# v100_ripping.net
KiCad netlist of a schematic drawn in EAGLE
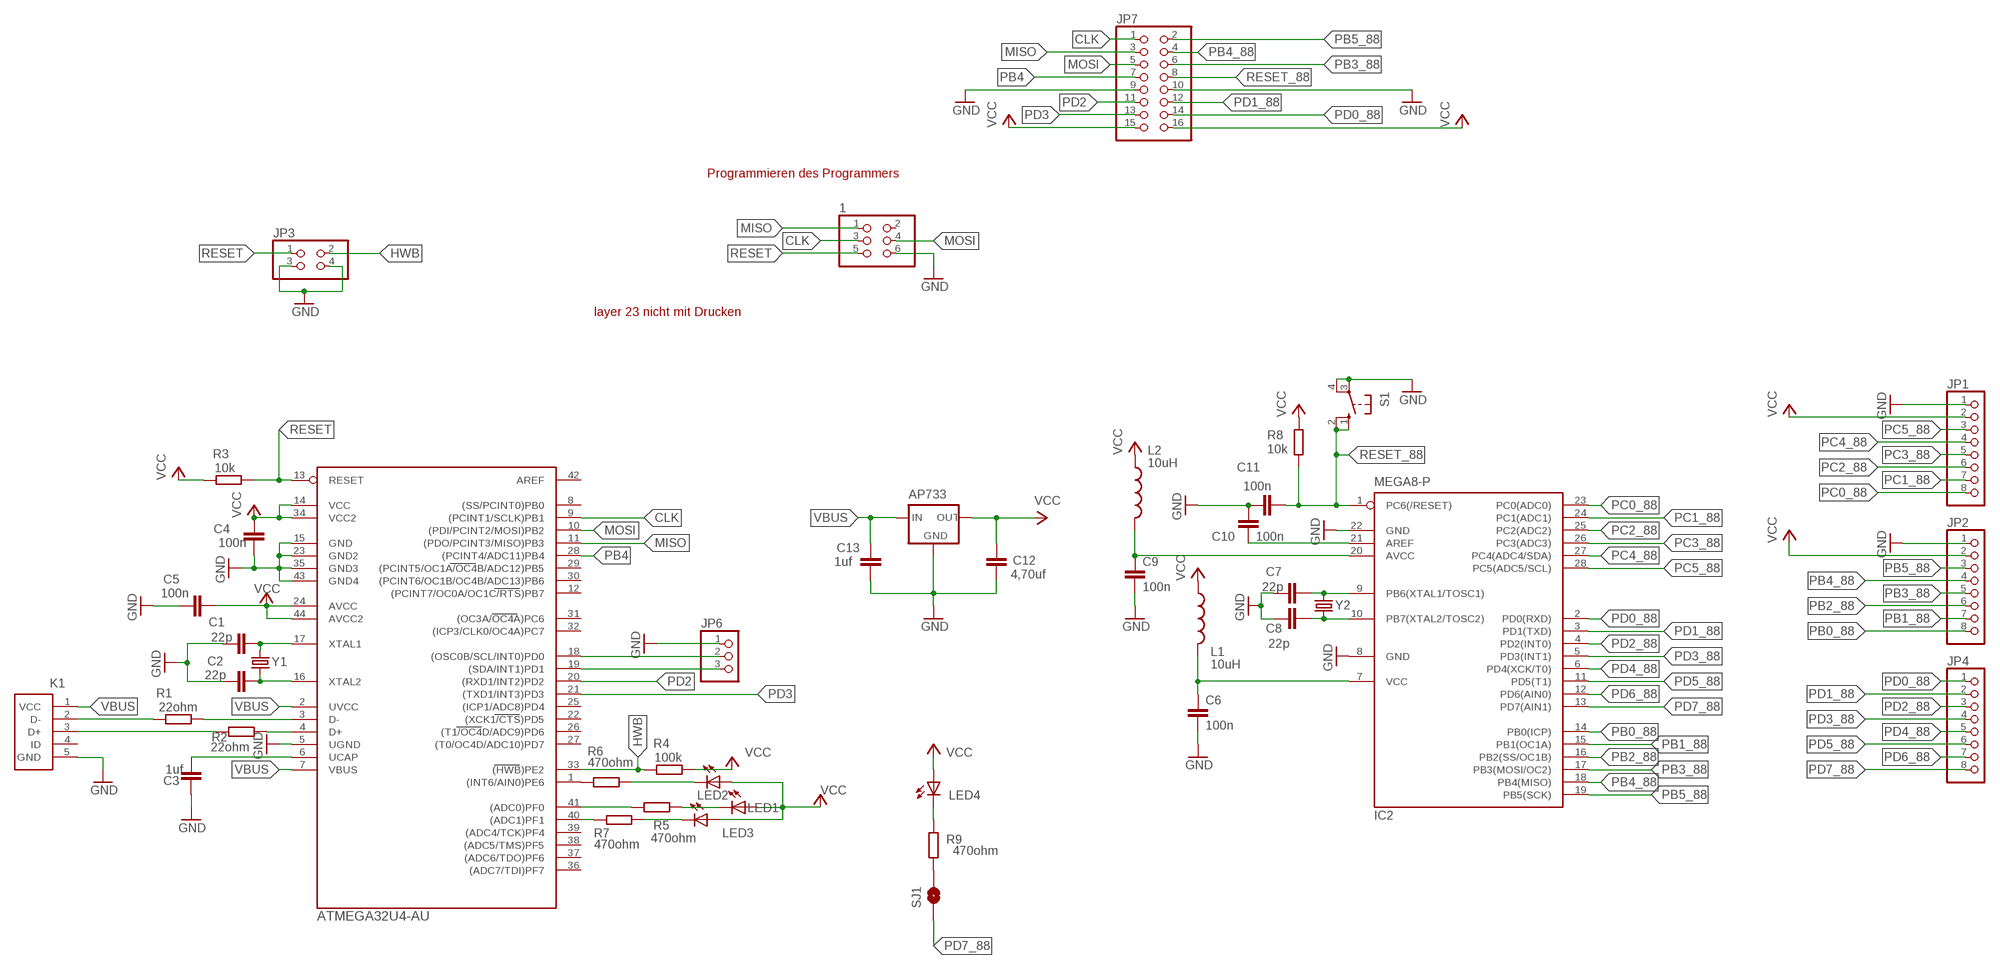
[diagram p0: schematic, sheet 1]

(export (version "E")
  (design (tool "Eeschema 10.0.6"))
  (components
    (comp (ref "1")
      (value "PINHD-2X3")
      (footprint "eagle-import:2X03")
      (libsource (lib "eagle-import") (part "PINHD-2X3"))
    )
    (comp (ref "C1")
      (value "22p")
      (footprint "eagle-import:C0805")
      (libsource (lib "eagle-import") (part "C-EUC0805"))
    )
    (comp (ref "C2")
      (value "22p")
      (footprint "eagle-import:C0805")
      (libsource (lib "eagle-import") (part "C-EUC0805"))
    )
    (comp (ref "C3")
      (value "1uf")
      (footprint "eagle-import:C0805")
      (libsource (lib "eagle-import") (part "C-EUC0805"))
    )
    (comp (ref "C4")
      (value "100n")
      (footprint "eagle-import:C0805")
      (libsource (lib "eagle-import") (part "C-EUC0805"))
    )
    (comp (ref "C5")
      (value "100n")
      (footprint "eagle-import:C0805")
      (libsource (lib "eagle-import") (part "C-EUC0805"))
    )
    (comp (ref "C6")
      (value "100n")
      (footprint "eagle-import:0805")
      (libsource (lib "eagle-import") (part "CAP0805"))
    )
    (comp (ref "C7")
      (value "22p")
      (footprint "eagle-import:C0805")
      (libsource (lib "eagle-import") (part "C-EUC0805"))
    )
    (comp (ref "C8")
      (value "22p")
      (footprint "eagle-import:C0805")
      (libsource (lib "eagle-import") (part "C-EUC0805"))
    )
    (comp (ref "C9")
      (value "100n")
      (footprint "eagle-import:0805")
      (libsource (lib "eagle-import") (part "CAP0805"))
    )
    (comp (ref "C10")
      (value "100n")
      (footprint "eagle-import:0805")
      (libsource (lib "eagle-import") (part "CAP0805"))
    )
    (comp (ref "C11")
      (value "100n")
      (footprint "eagle-import:0805")
      (libsource (lib "eagle-import") (part "CAP0805"))
    )
    (comp (ref "C12")
      (value "4,70uf")
      (footprint "eagle-import:C0805")
      (libsource (lib "eagle-import") (part "C-EUC0805"))
    )
    (comp (ref "C13")
      (value "1uf")
      (footprint "eagle-import:C0805")
      (libsource (lib "eagle-import") (part "C-EUC0805"))
    )
    (comp (ref "IC1")
      (value "ATMEGA32U4-AU")
      (footprint "eagle-import:TQFP44")
      (libsource (lib "eagle-import") (part "ATMEGA32U4-AU"))
    )
    (comp (ref "IC2")
      (value "MEGA8-P")
      (footprint "eagle-import:DIL28-3")
      (libsource (lib "eagle-import") (part "MEGA8-P"))
    )
    (comp (ref "JP1")
      (value "PINHD-1X8")
      (footprint "eagle-import:1X08")
      (libsource (lib "eagle-import") (part "PINHD-1X8"))
    )
    (comp (ref "JP2")
      (value "PINHD-1X8")
      (footprint "eagle-import:1X08")
      (libsource (lib "eagle-import") (part "PINHD-1X8"))
    )
    (comp (ref "JP3")
      (value "PINHD-2X2")
      (footprint "eagle-import:2X02")
      (libsource (lib "eagle-import") (part "PINHD-2X2"))
    )
    (comp (ref "JP4")
      (value "PINHD-1X8")
      (footprint "eagle-import:1X08")
      (libsource (lib "eagle-import") (part "PINHD-1X8"))
    )
    (comp (ref "JP6")
      (value "PINHD-1X3")
      (footprint "eagle-import:1X03")
      (libsource (lib "eagle-import") (part "PINHD-1X3"))
    )
    (comp (ref "JP7")
      (value "PINHD-2X8")
      (footprint "eagle-import:2X08")
      (libsource (lib "eagle-import") (part "PINHD-2X8"))
    )
    (comp (ref "K1")
      (value "65100516121")
      (footprint "eagle-import:65100516121")
      (libsource (lib "eagle-import") (part "65100516121"))
    )
    (comp (ref "L1")
      (value "10uH")
      (footprint "eagle-import:0805")
      (libsource (lib "eagle-import") (part "INDUCTOR0805"))
    )
    (comp (ref "L2")
      (value "10uH")
      (footprint "eagle-import:0805")
      (libsource (lib "eagle-import") (part "INDUCTOR0805"))
    )
    (comp (ref "LED1")
      (value "LED_LEDCHIP-LED0805")
      (footprint "eagle-import:LED_CHIP-LED0805")
      (libsource (lib "eagle-import") (part "LED_LEDCHIP-LED0805"))
    )
    (comp (ref "LED2")
      (value "LED_LEDCHIP-LED0805")
      (footprint "eagle-import:LED_CHIP-LED0805")
      (libsource (lib "eagle-import") (part "LED_LEDCHIP-LED0805"))
    )
    (comp (ref "LED3")
      (value "LED_LEDCHIP-LED0805")
      (footprint "eagle-import:LED_CHIP-LED0805")
      (libsource (lib "eagle-import") (part "LED_LEDCHIP-LED0805"))
    )
    (comp (ref "LED4")
      (value "LED_LEDCHIP-LED0805")
      (footprint "eagle-import:LED_CHIP-LED0805")
      (libsource (lib "eagle-import") (part "LED_LEDCHIP-LED0805"))
    )
    (comp (ref "R1")
      (value "22ohm")
      (footprint "eagle-import:R0805")
      (libsource (lib "eagle-import") (part "R-EU_R0805"))
    )
    (comp (ref "R2")
      (value "22ohm")
      (footprint "eagle-import:R0805")
      (libsource (lib "eagle-import") (part "R-EU_R0805"))
    )
    (comp (ref "R3")
      (value "10k")
      (footprint "eagle-import:R0805")
      (libsource (lib "eagle-import") (part "R-EU_R0805"))
    )
    (comp (ref "R4")
      (value "100k")
      (footprint "eagle-import:R0805")
      (libsource (lib "eagle-import") (part "R-EU_R0805"))
    )
    (comp (ref "R5")
      (value "470ohm")
      (footprint "eagle-import:R0805")
      (libsource (lib "eagle-import") (part "R-EU_R0805"))
    )
    (comp (ref "R6")
      (value "470ohm")
      (footprint "eagle-import:R0805")
      (libsource (lib "eagle-import") (part "R-EU_R0805"))
    )
    (comp (ref "R7")
      (value "470ohm")
      (footprint "eagle-import:R0805")
      (libsource (lib "eagle-import") (part "R-EU_R0805"))
    )
    (comp (ref "R8")
      (value "10k")
      (footprint "eagle-import:R0805")
      (libsource (lib "eagle-import") (part "R-EU_R0805"))
    )
    (comp (ref "R9")
      (value "470ohm")
      (footprint "eagle-import:R0805")
      (libsource (lib "eagle-import") (part "R-EU_R0805"))
    )
    (comp (ref "S1")
      (value "SWITCH-OMRON_10-XX")
      (footprint "eagle-import:SWITCH-OMRON_B3F-10XX")
      (fields (field (name "MPN") "B3F-1000"))
      (libsource (lib "eagle-import") (part "SWITCH-OMRON_10-XX"))
    )
    (comp (ref "SJ1")
      (value "SOLDERJUMPERTRACE")
      (footprint "eagle-import:SJ_2S-TRACE")
      (libsource (lib "eagle-import") (part "SOLDERJUMPERTRACE"))
    )
    (comp (ref "U$2")
      (value "AP733")
      (footprint "eagle-import:AP733")
      (libsource (lib "eagle-import") (part "AP733"))
    )
    (comp (ref "Y1")
      (value "CRYSTALSMD")
      (footprint "eagle-import:HC49UP")
      (libsource (lib "eagle-import") (part "CRYSTALSMD"))
    )
    (comp (ref "Y2")
      (value "CRYSTALSMD")
      (footprint "eagle-import:HC49UP")
      (libsource (lib "eagle-import") (part "CRYSTALSMD"))
    )
  )
  (nets
    (net (code "1") (name "CLK") (class "Default")
      (node (ref "1") (pin "3") (pinfunction "3_3") (pintype "passive"))
      (node (ref "IC1") (pin "9") (pinfunction "(PCINT1/SCLK)PB1_9") (pintype "bidirectional"))
      (node (ref "JP7") (pin "1") (pinfunction "1_1") (pintype "passive"))
    )
    (net (code "2") (name "GND") (class "Default")
      (node (ref "1") (pin "6") (pinfunction "6_6") (pintype "passive"))
      (node (ref "C1") (pin "1") (pinfunction "1_1") (pintype "passive"))
      (node (ref "C10") (pin "1") (pinfunction "1_1") (pintype "passive"))
      (node (ref "C11") (pin "1") (pinfunction "1_1") (pintype "passive"))
      (node (ref "C12") (pin "2") (pinfunction "2_2") (pintype "passive"))
      (node (ref "C13") (pin "2") (pinfunction "2_2") (pintype "passive"))
      (node (ref "C2") (pin "1") (pinfunction "1_1") (pintype "passive"))
      (node (ref "C3") (pin "1") (pinfunction "1_1") (pintype "passive"))
      (node (ref "C4") (pin "1") (pinfunction "1_1") (pintype "passive"))
      (node (ref "C5") (pin "2") (pinfunction "2_2") (pintype "passive"))
      (node (ref "C6") (pin "2") (pinfunction "2_2") (pintype "passive"))
      (node (ref "C7") (pin "1") (pinfunction "1_1") (pintype "passive"))
      (node (ref "C8") (pin "1") (pinfunction "1_1") (pintype "passive"))
      (node (ref "C9") (pin "2") (pinfunction "2_2") (pintype "passive"))
      (node (ref "IC1") (pin "15") (pinfunction "GND_15") (pintype "bidirectional"))
      (node (ref "IC1") (pin "23") (pinfunction "GND2_23") (pintype "bidirectional"))
      (node (ref "IC1") (pin "35") (pinfunction "GND3_35") (pintype "bidirectional"))
      (node (ref "IC1") (pin "43") (pinfunction "GND4_43") (pintype "bidirectional"))
      (node (ref "IC1") (pin "5") (pinfunction "UGND_5") (pintype "bidirectional"))
      (node (ref "IC2") (pin "22") (pinfunction "GND_22") (pintype "power_in"))
      (node (ref "IC2") (pin "8") (pinfunction "GND_8") (pintype "power_in"))
      (node (ref "JP1") (pin "1") (pinfunction "1_1") (pintype "passive"))
      (node (ref "JP2") (pin "1") (pinfunction "1_1") (pintype "passive"))
      (node (ref "JP3") (pin "3") (pinfunction "3_3") (pintype "passive"))
      (node (ref "JP3") (pin "4") (pinfunction "4_4") (pintype "passive"))
      (node (ref "JP6") (pin "1") (pinfunction "1_1") (pintype "passive"))
      (node (ref "JP7") (pin "10") (pinfunction "10_10") (pintype "passive"))
      (node (ref "JP7") (pin "9") (pinfunction "9_9") (pintype "passive"))
      (node (ref "K1") (pin "5") (pinfunction "GND_5") (pintype "passive"))
      (node (ref "S1") (pin "3") (pinfunction "P_3") (pintype "passive"))
      (node (ref "S1") (pin "4") (pinfunction "P1_4") (pintype "passive"))
      (node (ref "U$2") (pin "3") (pinfunction "GND_3") (pintype "input"))
    )
    (net (code "3") (name "HWB") (class "Default")
      (node (ref "IC1") (pin "33") (pinfunction "(HWB)PE2_33") (pintype "bidirectional"))
      (node (ref "JP3") (pin "2") (pinfunction "2_2") (pintype "passive"))
      (node (ref "R4") (pin "2") (pinfunction "2_2") (pintype "passive"))
    )
    (net (code "4") (name "MISO") (class "Default")
      (node (ref "1") (pin "1") (pinfunction "1_1") (pintype "passive"))
      (node (ref "IC1") (pin "11") (pinfunction "(PDO/PCINT3/MISO)PB3_11") (pintype "bidirectional"))
      (node (ref "JP7") (pin "3") (pinfunction "3_3") (pintype "passive"))
    )
    (net (code "5") (name "MOSI") (class "Default")
      (node (ref "1") (pin "4") (pinfunction "4_4") (pintype "passive"))
      (node (ref "IC1") (pin "10") (pinfunction "(PDI/PCINT2/MOSI)PB2_10") (pintype "bidirectional"))
      (node (ref "JP7") (pin "5") (pinfunction "5_5") (pintype "passive"))
    )
    (net (code "6") (name "Net-(IC1-(ADC0)PF0)") (class "Default")
      (node (ref "IC1") (pin "41") (pinfunction "(ADC0)PF0_41") (pintype "bidirectional"))
      (node (ref "R5") (pin "2") (pinfunction "2_2") (pintype "passive"))
    )
    (net (code "7") (name "Net-(IC1-(ADC1)PF1)") (class "Default")
      (node (ref "IC1") (pin "40") (pinfunction "(ADC1)PF1_40") (pintype "bidirectional"))
      (node (ref "R7") (pin "2") (pinfunction "2_2") (pintype "passive"))
    )
    (net (code "8") (name "Net-(IC1-(INT6{slash}AIN0)PE6)") (class "Default")
      (node (ref "IC1") (pin "1") (pinfunction "(INT6/AIN0)PE6_1") (pintype "bidirectional"))
      (node (ref "R6") (pin "2") (pinfunction "2_2") (pintype "passive"))
    )
    (net (code "9") (name "Net-(IC1-(OSC0B{slash}SCL{slash}INT0)PD0)") (class "Default")
      (node (ref "IC1") (pin "18") (pinfunction "(OSC0B/SCL/INT0)PD0_18") (pintype "bidirectional"))
      (node (ref "JP6") (pin "2") (pinfunction "2_2") (pintype "passive"))
    )
    (net (code "10") (name "Net-(IC1-(SDA{slash}INT1)PD1)") (class "Default")
      (node (ref "IC1") (pin "19") (pinfunction "(SDA/INT1)PD1_19") (pintype "bidirectional"))
      (node (ref "JP6") (pin "3") (pinfunction "3_3") (pintype "passive"))
    )
    (net (code "11") (name "Net-(IC1-D+)") (class "Default")
      (node (ref "IC1") (pin "4") (pinfunction "D+_4") (pintype "bidirectional"))
      (node (ref "R2") (pin "1") (pinfunction "1_1") (pintype "passive"))
    )
    (net (code "12") (name "Net-(IC1-D-)") (class "Default")
      (node (ref "IC1") (pin "3") (pinfunction "D-_3") (pintype "bidirectional"))
      (node (ref "R1") (pin "1") (pinfunction "1_1") (pintype "passive"))
    )
    (net (code "13") (name "Net-(IC1-UCAP)") (class "Default")
      (node (ref "C3") (pin "2") (pinfunction "2_2") (pintype "passive"))
      (node (ref "IC1") (pin "6") (pinfunction "UCAP_6") (pintype "bidirectional"))
    )
    (net (code "14") (name "Net-(IC1-XTAL1)") (class "Default")
      (node (ref "C1") (pin "2") (pinfunction "2_2") (pintype "passive"))
      (node (ref "IC1") (pin "17") (pinfunction "XTAL1_17") (pintype "bidirectional"))
      (node (ref "Y1") (pin "2") (pinfunction "2_2") (pintype "passive"))
    )
    (net (code "15") (name "Net-(IC1-XTAL2)") (class "Default")
      (node (ref "C2") (pin "2") (pinfunction "2_2") (pintype "passive"))
      (node (ref "IC1") (pin "16") (pinfunction "XTAL2_16") (pintype "bidirectional"))
      (node (ref "Y1") (pin "1") (pinfunction "1_1") (pintype "passive"))
    )
    (net (code "16") (name "Net-(IC2-AREF)") (class "Default")
      (node (ref "C10") (pin "2") (pinfunction "2_2") (pintype "passive"))
      (node (ref "IC2") (pin "21") (pinfunction "AREF_21") (pintype "passive"))
    )
    (net (code "17") (name "Net-(IC2-AVCC)") (class "Default")
      (node (ref "C9") (pin "1") (pinfunction "1_1") (pintype "passive"))
      (node (ref "IC2") (pin "20") (pinfunction "AVCC_20") (pintype "power_in"))
      (node (ref "L2") (pin "2") (pinfunction "2_2") (pintype "passive"))
    )
    (net (code "18") (name "Net-(IC2-PB6(XTAL1{slash}TOSC1))") (class "Default")
      (node (ref "C7") (pin "2") (pinfunction "2_2") (pintype "passive"))
      (node (ref "IC2") (pin "9") (pinfunction "PB6(XTAL1/TOSC1)_9") (pintype "bidirectional"))
      (node (ref "Y2") (pin "2") (pinfunction "2_2") (pintype "passive"))
    )
    (net (code "19") (name "Net-(IC2-PB7(XTAL2{slash}TOSC2))") (class "Default")
      (node (ref "C8") (pin "2") (pinfunction "2_2") (pintype "passive"))
      (node (ref "IC2") (pin "10") (pinfunction "PB7(XTAL2/TOSC2)_10") (pintype "bidirectional"))
      (node (ref "Y2") (pin "1") (pinfunction "1_1") (pintype "passive"))
    )
    (net (code "20") (name "Net-(IC2-VCC)") (class "Default")
      (node (ref "C6") (pin "1") (pinfunction "1_1") (pintype "passive"))
      (node (ref "IC2") (pin "7") (pinfunction "VCC_7") (pintype "power_in"))
      (node (ref "L1") (pin "2") (pinfunction "2_2") (pintype "passive"))
    )
    (net (code "21") (name "Net-(K1-D+)") (class "Default")
      (node (ref "K1") (pin "3") (pinfunction "D+_3") (pintype "passive"))
      (node (ref "R2") (pin "2") (pinfunction "2_2") (pintype "passive"))
    )
    (net (code "22") (name "Net-(K1-D-)") (class "Default")
      (node (ref "K1") (pin "2") (pinfunction "D-_2") (pintype "passive"))
      (node (ref "R1") (pin "2") (pinfunction "2_2") (pintype "passive"))
    )
    (net (code "23") (name "Net-(LED1-PadC)") (class "Default")
      (node (ref "LED1") (pin "C") (pinfunction "C_C") (pintype "passive"))
      (node (ref "R5") (pin "1") (pinfunction "1_1") (pintype "passive"))
    )
    (net (code "24") (name "Net-(LED2-PadC)") (class "Default")
      (node (ref "LED2") (pin "C") (pinfunction "C_C") (pintype "passive"))
      (node (ref "R6") (pin "1") (pinfunction "1_1") (pintype "passive"))
    )
    (net (code "25") (name "Net-(LED3-PadC)") (class "Default")
      (node (ref "LED3") (pin "C") (pinfunction "C_C") (pintype "passive"))
      (node (ref "R7") (pin "1") (pinfunction "1_1") (pintype "passive"))
    )
    (net (code "26") (name "Net-(LED4-PadC)") (class "Default")
      (node (ref "LED4") (pin "C") (pinfunction "C_C") (pintype "passive"))
      (node (ref "R9") (pin "1") (pinfunction "1_1") (pintype "passive"))
    )
    (net (code "27") (name "Net-(R9-Pad2)") (class "Default")
      (node (ref "R9") (pin "2") (pinfunction "2_2") (pintype "passive"))
      (node (ref "SJ1") (pin "2") (pinfunction "2_2") (pintype "passive"))
    )
    (net (code "28") (name "PB0_88") (class "Default")
      (node (ref "IC2") (pin "14") (pinfunction "PB0(ICP)_14") (pintype "bidirectional"))
      (node (ref "JP2") (pin "8") (pinfunction "8_8") (pintype "passive"))
    )
    (net (code "29") (name "PB1_88") (class "Default")
      (node (ref "IC2") (pin "15") (pinfunction "PB1(OC1A)_15") (pintype "bidirectional"))
      (node (ref "JP2") (pin "7") (pinfunction "7_7") (pintype "passive"))
    )
    (net (code "30") (name "PB2_88") (class "Default")
      (node (ref "IC2") (pin "16") (pinfunction "PB2(SS/OC1B)_16") (pintype "bidirectional"))
      (node (ref "JP2") (pin "6") (pinfunction "6_6") (pintype "passive"))
    )
    (net (code "31") (name "PB3_88") (class "Default")
      (node (ref "IC2") (pin "17") (pinfunction "PB3(MOSI/OC2)_17") (pintype "bidirectional"))
      (node (ref "JP2") (pin "5") (pinfunction "5_5") (pintype "passive"))
      (node (ref "JP7") (pin "6") (pinfunction "6_6") (pintype "passive"))
    )
    (net (code "32") (name "PB4") (class "Default")
      (node (ref "IC1") (pin "28") (pinfunction "(PCINT4/ADC11)PB4_28") (pintype "bidirectional"))
      (node (ref "JP7") (pin "7") (pinfunction "7_7") (pintype "passive"))
    )
    (net (code "33") (name "PB4_88") (class "Default")
      (node (ref "IC2") (pin "18") (pinfunction "PB4(MISO)_18") (pintype "bidirectional"))
      (node (ref "JP2") (pin "4") (pinfunction "4_4") (pintype "passive"))
      (node (ref "JP7") (pin "4") (pinfunction "4_4") (pintype "passive"))
    )
    (net (code "34") (name "PB5_88") (class "Default")
      (node (ref "IC2") (pin "19") (pinfunction "PB5(SCK)_19") (pintype "bidirectional"))
      (node (ref "JP2") (pin "3") (pinfunction "3_3") (pintype "passive"))
      (node (ref "JP7") (pin "2") (pinfunction "2_2") (pintype "passive"))
    )
    (net (code "35") (name "PC0_88") (class "Default")
      (node (ref "IC2") (pin "23") (pinfunction "PC0(ADC0)_23") (pintype "bidirectional"))
      (node (ref "JP1") (pin "8") (pinfunction "8_8") (pintype "passive"))
    )
    (net (code "36") (name "PC1_88") (class "Default")
      (node (ref "IC2") (pin "24") (pinfunction "PC1(ADC1)_24") (pintype "bidirectional"))
      (node (ref "JP1") (pin "7") (pinfunction "7_7") (pintype "passive"))
    )
    (net (code "37") (name "PC2_88") (class "Default")
      (node (ref "IC2") (pin "25") (pinfunction "PC2(ADC2)_25") (pintype "bidirectional"))
      (node (ref "JP1") (pin "6") (pinfunction "6_6") (pintype "passive"))
    )
    (net (code "38") (name "PC3_88") (class "Default")
      (node (ref "IC2") (pin "26") (pinfunction "PC3(ADC3)_26") (pintype "bidirectional"))
      (node (ref "JP1") (pin "5") (pinfunction "5_5") (pintype "passive"))
    )
    (net (code "39") (name "PC4_88") (class "Default")
      (node (ref "IC2") (pin "27") (pinfunction "PC4(ADC4/SDA)_27") (pintype "bidirectional"))
      (node (ref "JP1") (pin "4") (pinfunction "4_4") (pintype "passive"))
    )
    (net (code "40") (name "PC5_88") (class "Default")
      (node (ref "IC2") (pin "28") (pinfunction "PC5(ADC5/SCL)_28") (pintype "bidirectional"))
      (node (ref "JP1") (pin "3") (pinfunction "3_3") (pintype "passive"))
    )
    (net (code "41") (name "PD0_88") (class "Default")
      (node (ref "IC2") (pin "2") (pinfunction "PD0(RXD)_2") (pintype "bidirectional"))
      (node (ref "JP4") (pin "1") (pinfunction "1_1") (pintype "passive"))
      (node (ref "JP7") (pin "14") (pinfunction "14_14") (pintype "passive"))
    )
    (net (code "42") (name "PD1_88") (class "Default")
      (node (ref "IC2") (pin "3") (pinfunction "PD1(TXD)_3") (pintype "bidirectional"))
      (node (ref "JP4") (pin "2") (pinfunction "2_2") (pintype "passive"))
      (node (ref "JP7") (pin "12") (pinfunction "12_12") (pintype "passive"))
    )
    (net (code "43") (name "PD2") (class "Default")
      (node (ref "IC1") (pin "20") (pinfunction "(RXD1/INT2)PD2_20") (pintype "bidirectional"))
      (node (ref "JP7") (pin "11") (pinfunction "11_11") (pintype "passive"))
    )
    (net (code "44") (name "PD2_88") (class "Default")
      (node (ref "IC2") (pin "4") (pinfunction "PD2(INT0)_4") (pintype "bidirectional"))
      (node (ref "JP4") (pin "3") (pinfunction "3_3") (pintype "passive"))
    )
    (net (code "45") (name "PD3") (class "Default")
      (node (ref "IC1") (pin "21") (pinfunction "(TXD1/INT3)PD3_21") (pintype "bidirectional"))
      (node (ref "JP7") (pin "13") (pinfunction "13_13") (pintype "passive"))
    )
    (net (code "46") (name "PD3_88") (class "Default")
      (node (ref "IC2") (pin "5") (pinfunction "PD3(INT1)_5") (pintype "bidirectional"))
      (node (ref "JP4") (pin "4") (pinfunction "4_4") (pintype "passive"))
    )
    (net (code "47") (name "PD4_88") (class "Default")
      (node (ref "IC2") (pin "6") (pinfunction "PD4(XCK/T0)_6") (pintype "bidirectional"))
      (node (ref "JP4") (pin "5") (pinfunction "5_5") (pintype "passive"))
    )
    (net (code "48") (name "PD5_88") (class "Default")
      (node (ref "IC2") (pin "11") (pinfunction "PD5(T1)_11") (pintype "bidirectional"))
      (node (ref "JP4") (pin "6") (pinfunction "6_6") (pintype "passive"))
    )
    (net (code "49") (name "PD6_88") (class "Default")
      (node (ref "IC2") (pin "12") (pinfunction "PD6(AIN0)_12") (pintype "bidirectional"))
      (node (ref "JP4") (pin "7") (pinfunction "7_7") (pintype "passive"))
    )
    (net (code "50") (name "PD7_88") (class "Default")
      (node (ref "IC2") (pin "13") (pinfunction "PD7(AIN1)_13") (pintype "bidirectional"))
      (node (ref "JP4") (pin "8") (pinfunction "8_8") (pintype "passive"))
      (node (ref "SJ1") (pin "1") (pinfunction "1_1") (pintype "passive"))
    )
    (net (code "51") (name "RESET") (class "Default")
      (node (ref "1") (pin "5") (pinfunction "5_5") (pintype "passive"))
      (node (ref "IC1") (pin "13") (pinfunction "RESET_13") (pintype "bidirectional"))
      (node (ref "JP3") (pin "1") (pinfunction "1_1") (pintype "passive"))
      (node (ref "R3") (pin "1") (pinfunction "1_1") (pintype "passive"))
    )
    (net (code "52") (name "RESET_88") (class "Default")
      (node (ref "C11") (pin "2") (pinfunction "2_2") (pintype "passive"))
      (node (ref "IC2") (pin "1") (pinfunction "PC6(/RESET)_1") (pintype "bidirectional"))
      (node (ref "JP7") (pin "8") (pinfunction "8_8") (pintype "passive"))
      (node (ref "R8") (pin "1") (pinfunction "1_1") (pintype "passive"))
      (node (ref "S1") (pin "1") (pinfunction "S_1") (pintype "passive"))
      (node (ref "S1") (pin "2") (pinfunction "S1_2") (pintype "passive"))
    )
    (net (code "53") (name "VBUS") (class "Default")
      (node (ref "C13") (pin "1") (pinfunction "1_1") (pintype "passive"))
      (node (ref "IC1") (pin "2") (pinfunction "UVCC_2") (pintype "bidirectional"))
      (node (ref "IC1") (pin "7") (pinfunction "VBUS_7") (pintype "bidirectional"))
      (node (ref "K1") (pin "1") (pinfunction "VCC_1") (pintype "passive"))
      (node (ref "U$2") (pin "1") (pinfunction "IN_1") (pintype "input"))
    )
    (net (code "54") (name "VCC") (class "Default")
      (node (ref "C12") (pin "1") (pinfunction "1_1") (pintype "passive"))
      (node (ref "C4") (pin "2") (pinfunction "2_2") (pintype "passive"))
      (node (ref "C5") (pin "1") (pinfunction "1_1") (pintype "passive"))
      (node (ref "IC1") (pin "14") (pinfunction "VCC_14") (pintype "bidirectional"))
      (node (ref "IC1") (pin "24") (pinfunction "AVCC_24") (pintype "bidirectional"))
      (node (ref "IC1") (pin "34") (pinfunction "VCC2_34") (pintype "bidirectional"))
      (node (ref "IC1") (pin "44") (pinfunction "AVCC2_44") (pintype "bidirectional"))
      (node (ref "JP1") (pin "2") (pinfunction "2_2") (pintype "passive"))
      (node (ref "JP2") (pin "2") (pinfunction "2_2") (pintype "passive"))
      (node (ref "JP7") (pin "15") (pinfunction "15_15") (pintype "passive"))
      (node (ref "JP7") (pin "16") (pinfunction "16_16") (pintype "passive"))
      (node (ref "L1") (pin "1") (pinfunction "1_1") (pintype "passive"))
      (node (ref "L2") (pin "1") (pinfunction "1_1") (pintype "passive"))
      (node (ref "LED1") (pin "A") (pinfunction "A_A") (pintype "passive"))
      (node (ref "LED2") (pin "A") (pinfunction "A_A") (pintype "passive"))
      (node (ref "LED3") (pin "A") (pinfunction "A_A") (pintype "passive"))
      (node (ref "LED4") (pin "A") (pinfunction "A_A") (pintype "passive"))
      (node (ref "R3") (pin "2") (pinfunction "2_2") (pintype "passive"))
      (node (ref "R4") (pin "1") (pinfunction "1_1") (pintype "passive"))
      (node (ref "R8") (pin "2") (pinfunction "2_2") (pintype "passive"))
      (node (ref "U$2") (pin "2") (pinfunction "OUT_2") (pintype "output"))
    )
    (net (code "55") (name "unconnected-(1-Pad2)") (class "Default")
      (node (ref "1") (pin "2") (pinfunction "2_2") (pintype "passive"))
    )
    (net (code "56") (name "unconnected-(IC1-(ADC4{slash}TCK)PF4-Pad39)") (class "Default")
      (node (ref "IC1") (pin "39") (pinfunction "(ADC4/TCK)PF4_39") (pintype "bidirectional"))
    )
    (net (code "57") (name "unconnected-(IC1-(ADC5{slash}TMS)PF5-Pad38)") (class "Default")
      (node (ref "IC1") (pin "38") (pinfunction "(ADC5/TMS)PF5_38") (pintype "bidirectional"))
    )
    (net (code "58") (name "unconnected-(IC1-(ADC6{slash}TDO)PF6-Pad37)") (class "Default")
      (node (ref "IC1") (pin "37") (pinfunction "(ADC6/TDO)PF6_37") (pintype "bidirectional"))
    )
    (net (code "59") (name "unconnected-(IC1-(ADC7{slash}TDI)PF7-Pad36)") (class "Default")
      (node (ref "IC1") (pin "36") (pinfunction "(ADC7/TDI)PF7_36") (pintype "bidirectional"))
    )
    (net (code "60") (name "unconnected-(IC1-(ICP1{slash}ADC8)PD4-Pad25)") (class "Default")
      (node (ref "IC1") (pin "25") (pinfunction "(ICP1/ADC8)PD4_25") (pintype "bidirectional"))
    )
    (net (code "61") (name "unconnected-(IC1-(ICP3{slash}CLK0{slash}OC4A)PC7-Pad32)") (class "Default")
      (node (ref "IC1") (pin "32") (pinfunction "(ICP3/CLK0/OC4A)PC7_32") (pintype "bidirectional"))
    )
    (net (code "62") (name "unconnected-(IC1-(OC3A{slash}OC4A)PC6-Pad31)") (class "Default")
      (node (ref "IC1") (pin "31") (pinfunction "(OC3A/OC4A)PC6_31") (pintype "bidirectional"))
    )
    (net (code "63") (name "unconnected-(IC1-(PCINT5{slash}OC1A{slash}OC4B{slash}ADC12)PB5-Pad29)") (class "Default")
      (node (ref "IC1") (pin "29") (pinfunction "(PCINT5/OC1A/OC4B/ADC12)PB5_29") (pintype "bidirectional"))
    )
    (net (code "64") (name "unconnected-(IC1-(PCINT6{slash}OC1B{slash}OC4B{slash}ADC13)PB6-Pad30)") (class "Default")
      (node (ref "IC1") (pin "30") (pinfunction "(PCINT6/OC1B/OC4B/ADC13)PB6_30") (pintype "bidirectional"))
    )
    (net (code "65") (name "unconnected-(IC1-(PCINT7{slash}OC0A{slash}OC1C{slash}RTS)PB7-Pad12)") (class "Default")
      (node (ref "IC1") (pin "12") (pinfunction "(PCINT7/OC0A/OC1C/RTS)PB7_12") (pintype "bidirectional"))
    )
    (net (code "66") (name "unconnected-(IC1-(SS{slash}PCINT0)PB0-Pad8)") (class "Default")
      (node (ref "IC1") (pin "8") (pinfunction "(SS/PCINT0)PB0_8") (pintype "bidirectional"))
    )
    (net (code "67") (name "unconnected-(IC1-(T0{slash}OC4D{slash}ADC10)PD7-Pad27)") (class "Default")
      (node (ref "IC1") (pin "27") (pinfunction "(T0/OC4D/ADC10)PD7_27") (pintype "bidirectional"))
    )
    (net (code "68") (name "unconnected-(IC1-(T1{slash}OC4D{slash}ADC9)PD6-Pad26)") (class "Default")
      (node (ref "IC1") (pin "26") (pinfunction "(T1/OC4D/ADC9)PD6_26") (pintype "bidirectional"))
    )
    (net (code "69") (name "unconnected-(IC1-(XCK1{slash}CTS)PD5-Pad22)") (class "Default")
      (node (ref "IC1") (pin "22") (pinfunction "(XCK1/CTS)PD5_22") (pintype "bidirectional"))
    )
    (net (code "70") (name "unconnected-(IC1-AREF-Pad42)") (class "Default")
      (node (ref "IC1") (pin "42") (pinfunction "AREF_42") (pintype "bidirectional"))
    )
    (net (code "71") (name "unconnected-(K1-ID-Pad4)") (class "Default")
      (node (ref "K1") (pin "4") (pinfunction "ID_4") (pintype "passive"))
    )
  )
)
